# Main_DC-DC.net
KiCad netlist of a schematic drawn in Altium Designer
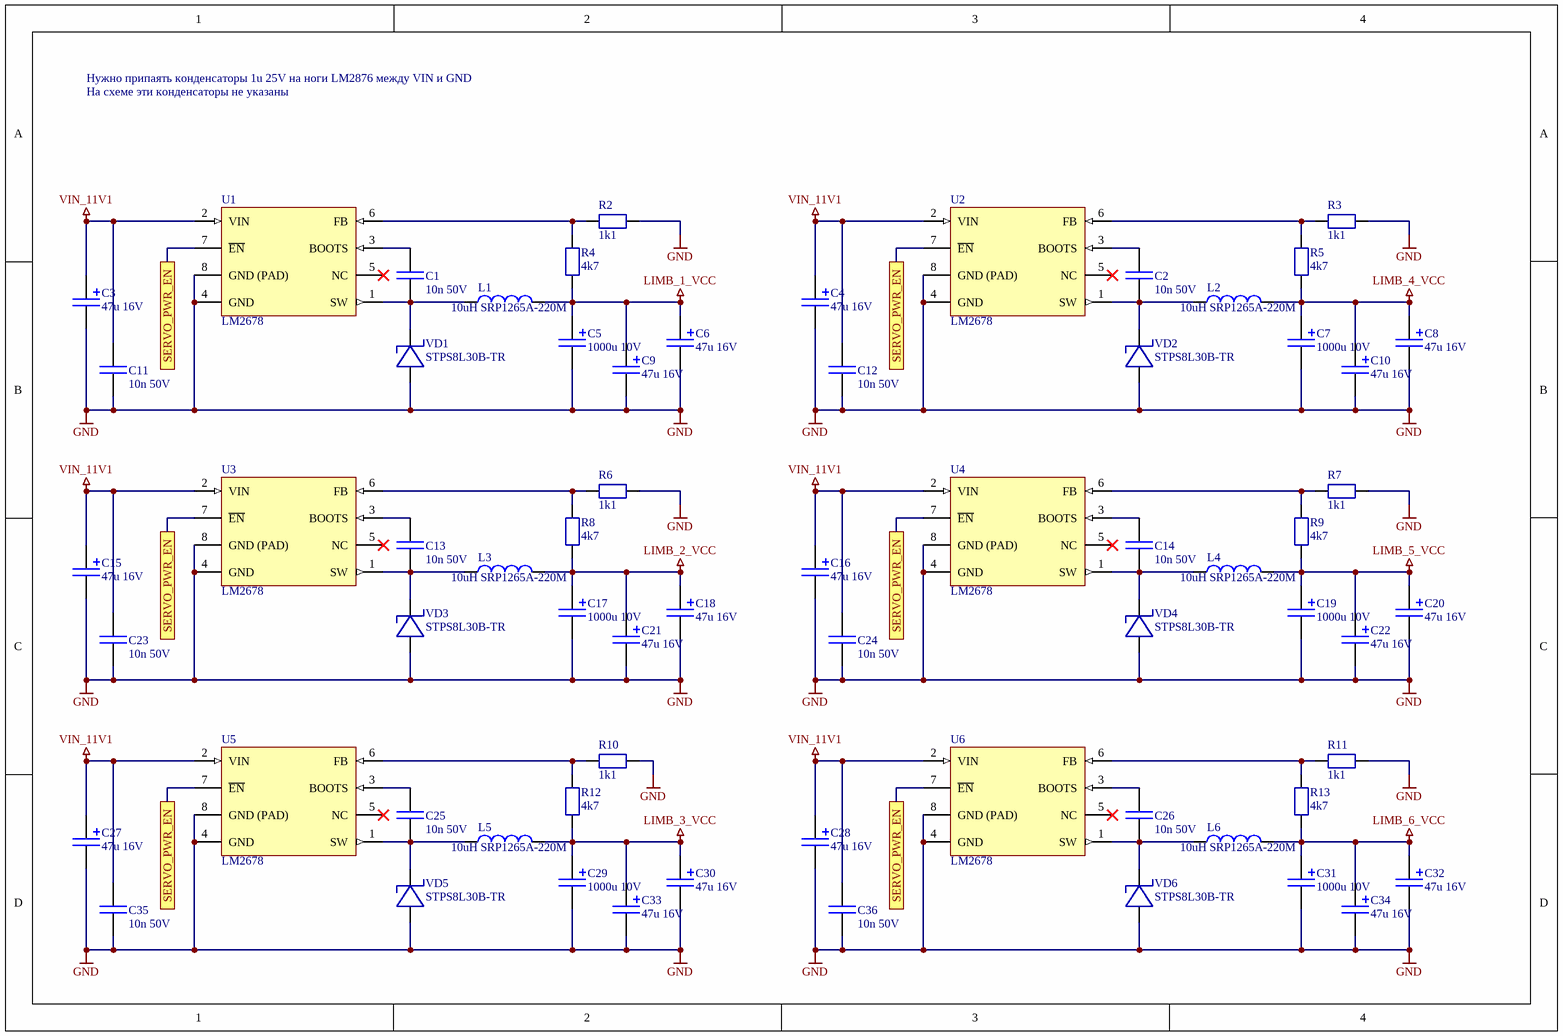
[diagram p0: Main DC-DC.SchDoc]

(export (version "E")
  (design (tool "Eeschema 10.0.6"))
  (components
    (comp (ref "C1")
      (value "10n 50V")
      (footprint "C_0805/2012")
      (description "Non-polarized capacitor")
      (libsource (lib "passive") (part "Capacitor"))
    )
    (comp (ref "C2")
      (value "10n 50V")
      (footprint "C_0805/2012")
      (description "Non-polarized capacitor")
      (libsource (lib "passive") (part "Capacitor"))
    )
    (comp (ref "C3")
      (value "47u 16V")
      (footprint "TECAP_TYPE_C")
      (description "Polarized capacitor")
      (libsource (lib "passive") (part "Capacitor polar"))
    )
    (comp (ref "C4")
      (value "47u 16V")
      (footprint "TECAP_TYPE_C")
      (description "Polarized capacitor")
      (libsource (lib "passive") (part "Capacitor polar"))
    )
    (comp (ref "C5")
      (value "1000u 10V")
      (footprint "ECAP_D10.0x10.5")
      (description "Polarized capacitor")
      (libsource (lib "passive") (part "Capacitor polar"))
    )
    (comp (ref "C6")
      (value "47u 16V")
      (footprint "TECAP_TYPE_D")
      (description "Polarized capacitor")
      (libsource (lib "passive") (part "Capacitor polar"))
    )
    (comp (ref "C7")
      (value "1000u 10V")
      (footprint "ECAP_D10.0x10.5")
      (description "Polarized capacitor")
      (libsource (lib "passive") (part "Capacitor polar"))
    )
    (comp (ref "C8")
      (value "47u 16V")
      (footprint "TECAP_TYPE_D")
      (description "Polarized capacitor")
      (libsource (lib "passive") (part "Capacitor polar"))
    )
    (comp (ref "C9")
      (value "47u 16V")
      (footprint "TECAP_TYPE_D")
      (description "Polarized capacitor")
      (libsource (lib "passive") (part "Capacitor polar"))
    )
    (comp (ref "C10")
      (value "47u 16V")
      (footprint "TECAP_TYPE_D")
      (description "Polarized capacitor")
      (libsource (lib "passive") (part "Capacitor polar"))
    )
    (comp (ref "C11")
      (value "10n 50V")
      (footprint "C_0805/2012")
      (description "Non-polarized capacitor")
      (libsource (lib "passive") (part "Capacitor"))
    )
    (comp (ref "C12")
      (value "10n 50V")
      (footprint "C_0805/2012")
      (description "Non-polarized capacitor")
      (libsource (lib "passive") (part "Capacitor"))
    )
    (comp (ref "C13")
      (value "10n 50V")
      (footprint "C_0805/2012")
      (description "Non-polarized capacitor")
      (libsource (lib "passive") (part "Capacitor"))
    )
    (comp (ref "C14")
      (value "10n 50V")
      (footprint "C_0805/2012")
      (description "Non-polarized capacitor")
      (libsource (lib "passive") (part "Capacitor"))
    )
    (comp (ref "C15")
      (value "47u 16V")
      (footprint "TECAP_TYPE_C")
      (description "Polarized capacitor")
      (libsource (lib "passive") (part "Capacitor polar"))
    )
    (comp (ref "C16")
      (value "47u 16V")
      (footprint "TECAP_TYPE_C")
      (description "Polarized capacitor")
      (libsource (lib "passive") (part "Capacitor polar"))
    )
    (comp (ref "C17")
      (value "1000u 10V")
      (footprint "ECAP_D10.0x10.5")
      (description "Polarized capacitor")
      (libsource (lib "passive") (part "Capacitor polar"))
    )
    (comp (ref "C18")
      (value "47u 16V")
      (footprint "TECAP_TYPE_D")
      (description "Polarized capacitor")
      (libsource (lib "passive") (part "Capacitor polar"))
    )
    (comp (ref "C19")
      (value "1000u 10V")
      (footprint "ECAP_D10.0x10.5")
      (description "Polarized capacitor")
      (libsource (lib "passive") (part "Capacitor polar"))
    )
    (comp (ref "C20")
      (value "47u 16V")
      (footprint "TECAP_TYPE_D")
      (description "Polarized capacitor")
      (libsource (lib "passive") (part "Capacitor polar"))
    )
    (comp (ref "C21")
      (value "47u 16V")
      (footprint "TECAP_TYPE_D")
      (description "Polarized capacitor")
      (libsource (lib "passive") (part "Capacitor polar"))
    )
    (comp (ref "C22")
      (value "47u 16V")
      (footprint "TECAP_TYPE_D")
      (description "Polarized capacitor")
      (libsource (lib "passive") (part "Capacitor polar"))
    )
    (comp (ref "C23")
      (value "10n 50V")
      (footprint "C_0805/2012")
      (description "Non-polarized capacitor")
      (libsource (lib "passive") (part "Capacitor"))
    )
    (comp (ref "C24")
      (value "10n 50V")
      (footprint "C_0805/2012")
      (description "Non-polarized capacitor")
      (libsource (lib "passive") (part "Capacitor"))
    )
    (comp (ref "C25")
      (value "10n 50V")
      (footprint "C_0805/2012")
      (description "Non-polarized capacitor")
      (libsource (lib "passive") (part "Capacitor"))
    )
    (comp (ref "C26")
      (value "10n 50V")
      (footprint "C_0805/2012")
      (description "Non-polarized capacitor")
      (libsource (lib "passive") (part "Capacitor"))
    )
    (comp (ref "C27")
      (value "47u 16V")
      (footprint "TECAP_TYPE_C")
      (description "Polarized capacitor")
      (libsource (lib "passive") (part "Capacitor polar"))
    )
    (comp (ref "C28")
      (value "47u 16V")
      (footprint "TECAP_TYPE_C")
      (description "Polarized capacitor")
      (libsource (lib "passive") (part "Capacitor polar"))
    )
    (comp (ref "C29")
      (value "1000u 10V")
      (footprint "ECAP_D10.0x10.5")
      (description "Polarized capacitor")
      (libsource (lib "passive") (part "Capacitor polar"))
    )
    (comp (ref "C30")
      (value "47u 16V")
      (footprint "TECAP_TYPE_D")
      (description "Polarized capacitor")
      (libsource (lib "passive") (part "Capacitor polar"))
    )
    (comp (ref "C31")
      (value "1000u 10V")
      (footprint "ECAP_D10.0x10.5")
      (description "Polarized capacitor")
      (libsource (lib "passive") (part "Capacitor polar"))
    )
    (comp (ref "C32")
      (value "47u 16V")
      (footprint "TECAP_TYPE_D")
      (description "Polarized capacitor")
      (libsource (lib "passive") (part "Capacitor polar"))
    )
    (comp (ref "C33")
      (value "47u 16V")
      (footprint "TECAP_TYPE_D")
      (description "Polarized capacitor")
      (libsource (lib "passive") (part "Capacitor polar"))
    )
    (comp (ref "C34")
      (value "47u 16V")
      (footprint "TECAP_TYPE_D")
      (description "Polarized capacitor")
      (libsource (lib "passive") (part "Capacitor polar"))
    )
    (comp (ref "C35")
      (value "10n 50V")
      (footprint "C_0805/2012")
      (description "Non-polarized capacitor")
      (libsource (lib "passive") (part "Capacitor"))
    )
    (comp (ref "C36")
      (value "10n 50V")
      (footprint "C_0805/2012")
      (description "Non-polarized capacitor")
      (libsource (lib "passive") (part "Capacitor"))
    )
    (comp (ref "L1")
      (value "10uH SRP1265A-220M")
      (footprint "L_13x13")
      (description "Inductor")
      (libsource (lib "passive") (part "Inductor"))
    )
    (comp (ref "L2")
      (value "10uH SRP1265A-220M")
      (footprint "L_13x13")
      (description "Inductor")
      (libsource (lib "passive") (part "Inductor"))
    )
    (comp (ref "L3")
      (value "10uH SRP1265A-220M")
      (footprint "L_13x13")
      (description "Inductor")
      (libsource (lib "passive") (part "Inductor"))
    )
    (comp (ref "L4")
      (value "10uH SRP1265A-220M")
      (footprint "L_13x13")
      (description "Inductor")
      (libsource (lib "passive") (part "Inductor"))
    )
    (comp (ref "L5")
      (value "10uH SRP1265A-220M")
      (footprint "L_13x13")
      (description "Inductor")
      (libsource (lib "passive") (part "Inductor"))
    )
    (comp (ref "L6")
      (value "10uH SRP1265A-220M")
      (footprint "L_13x13")
      (description "Inductor")
      (libsource (lib "passive") (part "Inductor"))
    )
    (comp (ref "R2")
      (value "1k1")
      (footprint "R_0805/2012")
      (description "Resistor")
      (libsource (lib "passive") (part "Resistor"))
    )
    (comp (ref "R3")
      (value "1k1")
      (footprint "R_0805/2012")
      (description "Resistor")
      (libsource (lib "passive") (part "Resistor"))
    )
    (comp (ref "R4")
      (value "4k7")
      (footprint "R_0805/2012")
      (description "Resistor")
      (libsource (lib "passive") (part "Resistor"))
    )
    (comp (ref "R5")
      (value "4k7")
      (footprint "R_0805/2012")
      (description "Resistor")
      (libsource (lib "passive") (part "Resistor"))
    )
    (comp (ref "R6")
      (value "1k1")
      (footprint "R_0805/2012")
      (description "Resistor")
      (libsource (lib "passive") (part "Resistor"))
    )
    (comp (ref "R7")
      (value "1k1")
      (footprint "R_0805/2012")
      (description "Resistor")
      (libsource (lib "passive") (part "Resistor"))
    )
    (comp (ref "R8")
      (value "4k7")
      (footprint "R_0805/2012")
      (description "Resistor")
      (libsource (lib "passive") (part "Resistor"))
    )
    (comp (ref "R9")
      (value "4k7")
      (footprint "R_0805/2012")
      (description "Resistor")
      (libsource (lib "passive") (part "Resistor"))
    )
    (comp (ref "R10")
      (value "1k1")
      (footprint "R_0805/2012")
      (description "Resistor")
      (libsource (lib "passive") (part "Resistor"))
    )
    (comp (ref "R11")
      (value "1k1")
      (footprint "R_0805/2012")
      (description "Resistor")
      (libsource (lib "passive") (part "Resistor"))
    )
    (comp (ref "R12")
      (value "4k7")
      (footprint "R_0805/2012")
      (description "Resistor")
      (libsource (lib "passive") (part "Resistor"))
    )
    (comp (ref "R13")
      (value "4k7")
      (footprint "R_0805/2012")
      (description "Resistor")
      (libsource (lib "passive") (part "Resistor"))
    )
    (comp (ref "U1")
      (value "LM2678")
      (footprint "TO263-7/D2PAK-7")
      (description "DC-DC step-down switching regulator")
      (libsource (lib "power") (part "LM2678"))
    )
    (comp (ref "U2")
      (value "LM2678")
      (footprint "TO263-7/D2PAK-7")
      (description "DC-DC step-down switching regulator")
      (libsource (lib "power") (part "LM2678"))
    )
    (comp (ref "U3")
      (value "LM2678")
      (footprint "TO263-7/D2PAK-7")
      (description "DC-DC step-down switching regulator")
      (libsource (lib "power") (part "LM2678"))
    )
    (comp (ref "U4")
      (value "LM2678")
      (footprint "TO263-7/D2PAK-7")
      (description "DC-DC step-down switching regulator")
      (libsource (lib "power") (part "LM2678"))
    )
    (comp (ref "U5")
      (value "LM2678")
      (footprint "TO263-7/D2PAK-7")
      (description "DC-DC step-down switching regulator")
      (libsource (lib "power") (part "LM2678"))
    )
    (comp (ref "U6")
      (value "LM2678")
      (footprint "TO263-7/D2PAK-7")
      (description "DC-DC step-down switching regulator")
      (libsource (lib "power") (part "LM2678"))
    )
    (comp (ref "VD1")
      (value "STPS8L30B-TR")
      (footprint "TO252AA/DPAK")
      (description "Schottky diode")
      (libsource (lib "active") (part "Schottky"))
    )
    (comp (ref "VD2")
      (value "STPS8L30B-TR")
      (footprint "TO252AA/DPAK")
      (description "Schottky diode")
      (libsource (lib "active") (part "Schottky"))
    )
    (comp (ref "VD3")
      (value "STPS8L30B-TR")
      (footprint "TO252AA/DPAK")
      (description "Schottky diode")
      (libsource (lib "active") (part "Schottky"))
    )
    (comp (ref "VD4")
      (value "STPS8L30B-TR")
      (footprint "TO252AA/DPAK")
      (description "Schottky diode")
      (libsource (lib "active") (part "Schottky"))
    )
    (comp (ref "VD5")
      (value "STPS8L30B-TR")
      (footprint "TO252AA/DPAK")
      (description "Schottky diode")
      (libsource (lib "active") (part "Schottky"))
    )
    (comp (ref "VD6")
      (value "STPS8L30B-TR")
      (footprint "TO252AA/DPAK")
      (description "Schottky diode")
      (libsource (lib "active") (part "Schottky"))
    )
  )
  (nets
    (net (code "1") (name "/SERVO_PWR_EN") (class "Default")
      (node (ref "U1") (pin "7") (pinfunction "~{EN}_7") (pintype "passive"))
      (node (ref "U2") (pin "7") (pinfunction "~{EN}_7") (pintype "passive"))
      (node (ref "U3") (pin "7") (pinfunction "~{EN}_7") (pintype "passive"))
      (node (ref "U4") (pin "7") (pinfunction "~{EN}_7") (pintype "passive"))
      (node (ref "U5") (pin "7") (pinfunction "~{EN}_7") (pintype "passive"))
      (node (ref "U6") (pin "7") (pinfunction "~{EN}_7") (pintype "passive"))
    )
    (net (code "2") (name "GND") (class "Default")
      (node (ref "C10") (pin "2") (pinfunction "NEG_2") (pintype "passive"))
      (node (ref "C11") (pin "2") (pintype "passive"))
      (node (ref "C12") (pin "2") (pintype "passive"))
      (node (ref "C15") (pin "2") (pinfunction "NEG_2") (pintype "passive"))
      (node (ref "C16") (pin "2") (pinfunction "NEG_2") (pintype "passive"))
      (node (ref "C17") (pin "2") (pinfunction "NEG_2") (pintype "passive"))
      (node (ref "C18") (pin "2") (pinfunction "NEG_2") (pintype "passive"))
      (node (ref "C19") (pin "2") (pinfunction "NEG_2") (pintype "passive"))
      (node (ref "C20") (pin "2") (pinfunction "NEG_2") (pintype "passive"))
      (node (ref "C21") (pin "2") (pinfunction "NEG_2") (pintype "passive"))
      (node (ref "C22") (pin "2") (pinfunction "NEG_2") (pintype "passive"))
      (node (ref "C23") (pin "2") (pintype "passive"))
      (node (ref "C24") (pin "2") (pintype "passive"))
      (node (ref "C27") (pin "2") (pinfunction "NEG_2") (pintype "passive"))
      (node (ref "C28") (pin "2") (pinfunction "NEG_2") (pintype "passive"))
      (node (ref "C29") (pin "2") (pinfunction "NEG_2") (pintype "passive"))
      (node (ref "C3") (pin "2") (pinfunction "NEG_2") (pintype "passive"))
      (node (ref "C30") (pin "2") (pinfunction "NEG_2") (pintype "passive"))
      (node (ref "C31") (pin "2") (pinfunction "NEG_2") (pintype "passive"))
      (node (ref "C32") (pin "2") (pinfunction "NEG_2") (pintype "passive"))
      (node (ref "C33") (pin "2") (pinfunction "NEG_2") (pintype "passive"))
      (node (ref "C34") (pin "2") (pinfunction "NEG_2") (pintype "passive"))
      (node (ref "C35") (pin "2") (pintype "passive"))
      (node (ref "C36") (pin "2") (pintype "passive"))
      (node (ref "C4") (pin "2") (pinfunction "NEG_2") (pintype "passive"))
      (node (ref "C5") (pin "2") (pinfunction "NEG_2") (pintype "passive"))
      (node (ref "C6") (pin "2") (pinfunction "NEG_2") (pintype "passive"))
      (node (ref "C7") (pin "2") (pinfunction "NEG_2") (pintype "passive"))
      (node (ref "C8") (pin "2") (pinfunction "NEG_2") (pintype "passive"))
      (node (ref "C9") (pin "2") (pinfunction "NEG_2") (pintype "passive"))
      (node (ref "R10") (pin "2") (pintype "passive"))
      (node (ref "R11") (pin "2") (pintype "passive"))
      (node (ref "R2") (pin "2") (pintype "passive"))
      (node (ref "R3") (pin "2") (pintype "passive"))
      (node (ref "R6") (pin "2") (pintype "passive"))
      (node (ref "R7") (pin "2") (pintype "passive"))
      (node (ref "U1") (pin "4") (pinfunction "GND_4") (pintype "passive"))
      (node (ref "U1") (pin "8") (pinfunction "GND_(PAD)_8") (pintype "passive"))
      (node (ref "U2") (pin "4") (pinfunction "GND_4") (pintype "passive"))
      (node (ref "U2") (pin "8") (pinfunction "GND_(PAD)_8") (pintype "passive"))
      (node (ref "U3") (pin "4") (pinfunction "GND_4") (pintype "passive"))
      (node (ref "U3") (pin "8") (pinfunction "GND_(PAD)_8") (pintype "passive"))
      (node (ref "U4") (pin "4") (pinfunction "GND_4") (pintype "passive"))
      (node (ref "U4") (pin "8") (pinfunction "GND_(PAD)_8") (pintype "passive"))
      (node (ref "U5") (pin "4") (pinfunction "GND_4") (pintype "passive"))
      (node (ref "U5") (pin "8") (pinfunction "GND_(PAD)_8") (pintype "passive"))
      (node (ref "U6") (pin "4") (pinfunction "GND_4") (pintype "passive"))
      (node (ref "U6") (pin "8") (pinfunction "GND_(PAD)_8") (pintype "passive"))
      (node (ref "VD1") (pin "1") (pinfunction "1_1") (pintype "passive"))
      (node (ref "VD2") (pin "1") (pinfunction "1_1") (pintype "passive"))
      (node (ref "VD3") (pin "1") (pinfunction "1_1") (pintype "passive"))
      (node (ref "VD4") (pin "1") (pinfunction "1_1") (pintype "passive"))
      (node (ref "VD5") (pin "1") (pinfunction "1_1") (pintype "passive"))
      (node (ref "VD6") (pin "1") (pinfunction "1_1") (pintype "passive"))
    )
    (net (code "3") (name "LIMB_1_VCC") (class "Default")
      (node (ref "C5") (pin "1") (pinfunction "POS_1") (pintype "passive"))
      (node (ref "C6") (pin "1") (pinfunction "POS_1") (pintype "passive"))
      (node (ref "C9") (pin "1") (pinfunction "POS_1") (pintype "passive"))
      (node (ref "L1") (pin "2") (pintype "passive"))
      (node (ref "R4") (pin "2") (pintype "passive"))
    )
    (net (code "4") (name "LIMB_2_VCC") (class "Default")
      (node (ref "C17") (pin "1") (pinfunction "POS_1") (pintype "passive"))
      (node (ref "C18") (pin "1") (pinfunction "POS_1") (pintype "passive"))
      (node (ref "C21") (pin "1") (pinfunction "POS_1") (pintype "passive"))
      (node (ref "L3") (pin "2") (pintype "passive"))
      (node (ref "R8") (pin "2") (pintype "passive"))
    )
    (net (code "5") (name "LIMB_3_VCC") (class "Default")
      (node (ref "C29") (pin "1") (pinfunction "POS_1") (pintype "passive"))
      (node (ref "C30") (pin "1") (pinfunction "POS_1") (pintype "passive"))
      (node (ref "C33") (pin "1") (pinfunction "POS_1") (pintype "passive"))
      (node (ref "L5") (pin "2") (pintype "passive"))
      (node (ref "R12") (pin "2") (pintype "passive"))
    )
    (net (code "6") (name "LIMB_4_VCC") (class "Default")
      (node (ref "C10") (pin "1") (pinfunction "POS_1") (pintype "passive"))
      (node (ref "C7") (pin "1") (pinfunction "POS_1") (pintype "passive"))
      (node (ref "C8") (pin "1") (pinfunction "POS_1") (pintype "passive"))
      (node (ref "L2") (pin "2") (pintype "passive"))
      (node (ref "R5") (pin "2") (pintype "passive"))
    )
    (net (code "7") (name "LIMB_5_VCC") (class "Default")
      (node (ref "C19") (pin "1") (pinfunction "POS_1") (pintype "passive"))
      (node (ref "C20") (pin "1") (pinfunction "POS_1") (pintype "passive"))
      (node (ref "C22") (pin "1") (pinfunction "POS_1") (pintype "passive"))
      (node (ref "L4") (pin "2") (pintype "passive"))
      (node (ref "R9") (pin "2") (pintype "passive"))
    )
    (net (code "8") (name "LIMB_6_VCC") (class "Default")
      (node (ref "C31") (pin "1") (pinfunction "POS_1") (pintype "passive"))
      (node (ref "C32") (pin "1") (pinfunction "POS_1") (pintype "passive"))
      (node (ref "C34") (pin "1") (pinfunction "POS_1") (pintype "passive"))
      (node (ref "L6") (pin "2") (pintype "passive"))
      (node (ref "R13") (pin "2") (pintype "passive"))
    )
    (net (code "9") (name "Net-(U1-BOOTS)") (class "Default")
      (node (ref "C1") (pin "1") (pintype "passive"))
      (node (ref "U1") (pin "3") (pinfunction "BOOTS_3") (pintype "input"))
    )
    (net (code "10") (name "Net-(U1-FB)") (class "Default")
      (node (ref "R2") (pin "1") (pintype "passive"))
      (node (ref "R4") (pin "1") (pintype "passive"))
      (node (ref "U1") (pin "6") (pinfunction "FB_6") (pintype "input"))
    )
    (net (code "11") (name "Net-(U1-SW)") (class "Default")
      (node (ref "C1") (pin "2") (pintype "passive"))
      (node (ref "L1") (pin "1") (pintype "passive"))
      (node (ref "U1") (pin "1") (pinfunction "SW_1") (pintype "output"))
      (node (ref "VD1") (pin "2") (pinfunction "2_2") (pintype "passive"))
    )
    (net (code "12") (name "Net-(U2-BOOTS)") (class "Default")
      (node (ref "C2") (pin "1") (pintype "passive"))
      (node (ref "U2") (pin "3") (pinfunction "BOOTS_3") (pintype "input"))
    )
    (net (code "13") (name "Net-(U2-FB)") (class "Default")
      (node (ref "R3") (pin "1") (pintype "passive"))
      (node (ref "R5") (pin "1") (pintype "passive"))
      (node (ref "U2") (pin "6") (pinfunction "FB_6") (pintype "input"))
    )
    (net (code "14") (name "Net-(U2-SW)") (class "Default")
      (node (ref "C2") (pin "2") (pintype "passive"))
      (node (ref "L2") (pin "1") (pintype "passive"))
      (node (ref "U2") (pin "1") (pinfunction "SW_1") (pintype "output"))
      (node (ref "VD2") (pin "2") (pinfunction "2_2") (pintype "passive"))
    )
    (net (code "15") (name "Net-(U3-BOOTS)") (class "Default")
      (node (ref "C13") (pin "1") (pintype "passive"))
      (node (ref "U3") (pin "3") (pinfunction "BOOTS_3") (pintype "input"))
    )
    (net (code "16") (name "Net-(U3-FB)") (class "Default")
      (node (ref "R6") (pin "1") (pintype "passive"))
      (node (ref "R8") (pin "1") (pintype "passive"))
      (node (ref "U3") (pin "6") (pinfunction "FB_6") (pintype "input"))
    )
    (net (code "17") (name "Net-(U3-SW)") (class "Default")
      (node (ref "C13") (pin "2") (pintype "passive"))
      (node (ref "L3") (pin "1") (pintype "passive"))
      (node (ref "U3") (pin "1") (pinfunction "SW_1") (pintype "output"))
      (node (ref "VD3") (pin "2") (pinfunction "2_2") (pintype "passive"))
    )
    (net (code "18") (name "Net-(U4-BOOTS)") (class "Default")
      (node (ref "C14") (pin "1") (pintype "passive"))
      (node (ref "U4") (pin "3") (pinfunction "BOOTS_3") (pintype "input"))
    )
    (net (code "19") (name "Net-(U4-FB)") (class "Default")
      (node (ref "R7") (pin "1") (pintype "passive"))
      (node (ref "R9") (pin "1") (pintype "passive"))
      (node (ref "U4") (pin "6") (pinfunction "FB_6") (pintype "input"))
    )
    (net (code "20") (name "Net-(U4-SW)") (class "Default")
      (node (ref "C14") (pin "2") (pintype "passive"))
      (node (ref "L4") (pin "1") (pintype "passive"))
      (node (ref "U4") (pin "1") (pinfunction "SW_1") (pintype "output"))
      (node (ref "VD4") (pin "2") (pinfunction "2_2") (pintype "passive"))
    )
    (net (code "21") (name "Net-(U5-BOOTS)") (class "Default")
      (node (ref "C25") (pin "1") (pintype "passive"))
      (node (ref "U5") (pin "3") (pinfunction "BOOTS_3") (pintype "input"))
    )
    (net (code "22") (name "Net-(U5-FB)") (class "Default")
      (node (ref "R10") (pin "1") (pintype "passive"))
      (node (ref "R12") (pin "1") (pintype "passive"))
      (node (ref "U5") (pin "6") (pinfunction "FB_6") (pintype "input"))
    )
    (net (code "23") (name "Net-(U5-SW)") (class "Default")
      (node (ref "C25") (pin "2") (pintype "passive"))
      (node (ref "L5") (pin "1") (pintype "passive"))
      (node (ref "U5") (pin "1") (pinfunction "SW_1") (pintype "output"))
      (node (ref "VD5") (pin "2") (pinfunction "2_2") (pintype "passive"))
    )
    (net (code "24") (name "Net-(U6-BOOTS)") (class "Default")
      (node (ref "C26") (pin "1") (pintype "passive"))
      (node (ref "U6") (pin "3") (pinfunction "BOOTS_3") (pintype "input"))
    )
    (net (code "25") (name "Net-(U6-FB)") (class "Default")
      (node (ref "R11") (pin "1") (pintype "passive"))
      (node (ref "R13") (pin "1") (pintype "passive"))
      (node (ref "U6") (pin "6") (pinfunction "FB_6") (pintype "input"))
    )
    (net (code "26") (name "Net-(U6-SW)") (class "Default")
      (node (ref "C26") (pin "2") (pintype "passive"))
      (node (ref "L6") (pin "1") (pintype "passive"))
      (node (ref "U6") (pin "1") (pinfunction "SW_1") (pintype "output"))
      (node (ref "VD6") (pin "2") (pinfunction "2_2") (pintype "passive"))
    )
    (net (code "27") (name "VIN_11V1") (class "Default")
      (node (ref "C11") (pin "1") (pintype "passive"))
      (node (ref "C12") (pin "1") (pintype "passive"))
      (node (ref "C15") (pin "1") (pinfunction "POS_1") (pintype "passive"))
      (node (ref "C16") (pin "1") (pinfunction "POS_1") (pintype "passive"))
      (node (ref "C23") (pin "1") (pintype "passive"))
      (node (ref "C24") (pin "1") (pintype "passive"))
      (node (ref "C27") (pin "1") (pinfunction "POS_1") (pintype "passive"))
      (node (ref "C28") (pin "1") (pinfunction "POS_1") (pintype "passive"))
      (node (ref "C3") (pin "1") (pinfunction "POS_1") (pintype "passive"))
      (node (ref "C35") (pin "1") (pintype "passive"))
      (node (ref "C36") (pin "1") (pintype "passive"))
      (node (ref "C4") (pin "1") (pinfunction "POS_1") (pintype "passive"))
      (node (ref "U1") (pin "2") (pinfunction "VIN_2") (pintype "input"))
      (node (ref "U2") (pin "2") (pinfunction "VIN_2") (pintype "input"))
      (node (ref "U3") (pin "2") (pinfunction "VIN_2") (pintype "input"))
      (node (ref "U4") (pin "2") (pinfunction "VIN_2") (pintype "input"))
      (node (ref "U5") (pin "2") (pinfunction "VIN_2") (pintype "input"))
      (node (ref "U6") (pin "2") (pinfunction "VIN_2") (pintype "input"))
    )
    (net (code "28") (name "unconnected-(U1-NC-Pad5)") (class "Default")
      (node (ref "U1") (pin "5") (pinfunction "NC_5") (pintype "passive+no_connect"))
    )
    (net (code "29") (name "unconnected-(U2-NC-Pad5)") (class "Default")
      (node (ref "U2") (pin "5") (pinfunction "NC_5") (pintype "passive+no_connect"))
    )
    (net (code "30") (name "unconnected-(U3-NC-Pad5)") (class "Default")
      (node (ref "U3") (pin "5") (pinfunction "NC_5") (pintype "passive+no_connect"))
    )
    (net (code "31") (name "unconnected-(U4-NC-Pad5)") (class "Default")
      (node (ref "U4") (pin "5") (pinfunction "NC_5") (pintype "passive+no_connect"))
    )
    (net (code "32") (name "unconnected-(U5-NC-Pad5)") (class "Default")
      (node (ref "U5") (pin "5") (pinfunction "NC_5") (pintype "passive+no_connect"))
    )
    (net (code "33") (name "unconnected-(U6-NC-Pad5)") (class "Default")
      (node (ref "U6") (pin "5") (pinfunction "NC_5") (pintype "passive+no_connect"))
    )
  )
)
